# RGBTemp.net
KiCad netlist of a schematic drawn in EAGLE
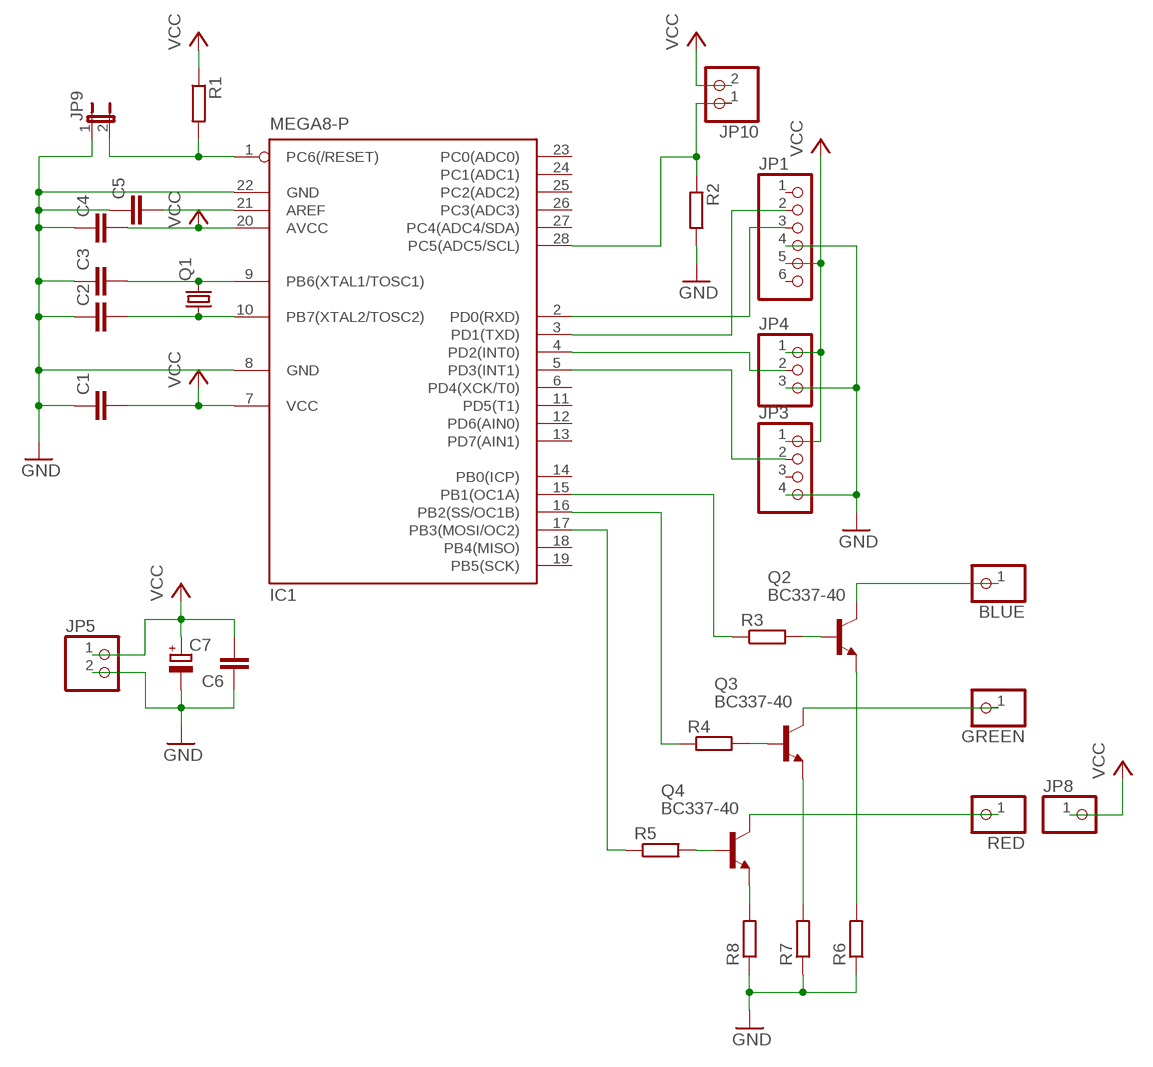
[diagram p0: schematic, sheet 1]

(export (version "E")
  (design (tool "Eeschema 10.0.6"))
  (components
    (comp (ref "BLUE")
      (value "PINHD-1X1")
      (footprint "eagle-import:1X01")
      (libsource (lib "eagle-import") (part "PINHD-1X1"))
    )
    (comp (ref "C1")
      (value "C-EU025-025X050")
      (footprint "eagle-import:C025-025X050")
      (libsource (lib "eagle-import") (part "C-EU025-025X050"))
    )
    (comp (ref "C2")
      (value "C-EU025-025X050")
      (footprint "eagle-import:C025-025X050")
      (libsource (lib "eagle-import") (part "C-EU025-025X050"))
    )
    (comp (ref "C3")
      (value "C-EU025-025X050")
      (footprint "eagle-import:C025-025X050")
      (libsource (lib "eagle-import") (part "C-EU025-025X050"))
    )
    (comp (ref "C4")
      (value "C-EU025-025X050")
      (footprint "eagle-import:C025-025X050")
      (libsource (lib "eagle-import") (part "C-EU025-025X050"))
    )
    (comp (ref "C5")
      (value "C-EU025-025X050")
      (footprint "eagle-import:C025-025X050")
      (libsource (lib "eagle-import") (part "C-EU025-025X050"))
    )
    (comp (ref "C6")
      (value "C-EU025-025X050")
      (footprint "eagle-import:C025-025X050")
      (libsource (lib "eagle-import") (part "C-EU025-025X050"))
    )
    (comp (ref "C7")
      (value "CPOL-EUE5-8.5")
      (footprint "eagle-import:E5-8,5")
      (libsource (lib "eagle-import") (part "CPOL-EUE5-8.5"))
    )
    (comp (ref "GREEN")
      (value "PINHD-1X1")
      (footprint "eagle-import:1X01")
      (libsource (lib "eagle-import") (part "PINHD-1X1"))
    )
    (comp (ref "IC1")
      (value "MEGA8-P")
      (footprint "eagle-import:DIL28-3")
      (libsource (lib "eagle-import") (part "MEGA8-P"))
    )
    (comp (ref "JP1")
      (value "PINHD-1X6")
      (footprint "eagle-import:1X06")
      (libsource (lib "eagle-import") (part "PINHD-1X6"))
    )
    (comp (ref "JP3")
      (value "PINHD-1X4")
      (footprint "eagle-import:1X04")
      (libsource (lib "eagle-import") (part "PINHD-1X4"))
    )
    (comp (ref "JP4")
      (value "PINHD-1X3")
      (footprint "eagle-import:1X03")
      (libsource (lib "eagle-import") (part "PINHD-1X3"))
    )
    (comp (ref "JP5")
      (value "PINHD-1X2")
      (footprint "eagle-import:1X02")
      (libsource (lib "eagle-import") (part "PINHD-1X2"))
    )
    (comp (ref "JP8")
      (value "PINHD-1X1")
      (footprint "eagle-import:1X01")
      (libsource (lib "eagle-import") (part "PINHD-1X1"))
    )
    (comp (ref "JP9")
      (value "JP1E")
      (footprint "eagle-import:JP1")
      (libsource (lib "eagle-import") (part "JP1E"))
    )
    (comp (ref "JP10")
      (value "PINHD-1X2")
      (footprint "eagle-import:1X02")
      (libsource (lib "eagle-import") (part "PINHD-1X2"))
    )
    (comp (ref "Q1")
      (value "CRYSTALHC49U-V")
      (footprint "eagle-import:HC49U-V")
      (libsource (lib "eagle-import") (part "CRYSTALHC49U-V"))
    )
    (comp (ref "Q2")
      (value "BC337-40")
      (footprint "eagle-import:TO92")
      (libsource (lib "eagle-import") (part "BC337-40"))
    )
    (comp (ref "Q3")
      (value "BC337-40")
      (footprint "eagle-import:TO92")
      (libsource (lib "eagle-import") (part "BC337-40"))
    )
    (comp (ref "Q4")
      (value "BC337-40")
      (footprint "eagle-import:TO92")
      (libsource (lib "eagle-import") (part "BC337-40"))
    )
    (comp (ref "R1")
      (value "R-EU_R1206")
      (footprint "eagle-import:R1206")
      (libsource (lib "eagle-import") (part "R-EU_R1206"))
    )
    (comp (ref "R2")
      (value "R-EU_R1206")
      (footprint "eagle-import:R1206")
      (libsource (lib "eagle-import") (part "R-EU_R1206"))
    )
    (comp (ref "R3")
      (value "R-EU_R1206")
      (footprint "eagle-import:R1206")
      (libsource (lib "eagle-import") (part "R-EU_R1206"))
    )
    (comp (ref "R4")
      (value "R-EU_R1206")
      (footprint "eagle-import:R1206")
      (libsource (lib "eagle-import") (part "R-EU_R1206"))
    )
    (comp (ref "R5")
      (value "R-EU_R1206")
      (footprint "eagle-import:R1206")
      (libsource (lib "eagle-import") (part "R-EU_R1206"))
    )
    (comp (ref "R6")
      (value "R-EU_0207/2V")
      (footprint "eagle-import:0207_2V")
      (libsource (lib "eagle-import") (part "R-EU_0207/2V"))
    )
    (comp (ref "R7")
      (value "R-EU_0207/2V")
      (footprint "eagle-import:0207_2V")
      (libsource (lib "eagle-import") (part "R-EU_0207/2V"))
    )
    (comp (ref "R8")
      (value "R-EU_0207/2V")
      (footprint "eagle-import:0207_2V")
      (libsource (lib "eagle-import") (part "R-EU_0207/2V"))
    )
    (comp (ref "RED")
      (value "PINHD-1X1")
      (footprint "eagle-import:1X01")
      (libsource (lib "eagle-import") (part "PINHD-1X1"))
    )
  )
  (nets
    (net (code "1") (name "GND") (class "Default")
      (node (ref "C1") (pin "1") (pinfunction "1_1") (pintype "passive"))
      (node (ref "C2") (pin "1") (pinfunction "1_1") (pintype "passive"))
      (node (ref "C3") (pin "1") (pinfunction "1_1") (pintype "passive"))
      (node (ref "C4") (pin "1") (pinfunction "1_1") (pintype "passive"))
      (node (ref "C5") (pin "1") (pinfunction "1_1") (pintype "passive"))
      (node (ref "C6") (pin "1") (pinfunction "1_1") (pintype "passive"))
      (node (ref "C7") (pin "-") (pinfunction "-_-") (pintype "passive"))
      (node (ref "IC1") (pin "22") (pinfunction "GND_22") (pintype "power_in"))
      (node (ref "IC1") (pin "8") (pinfunction "GND_8") (pintype "power_in"))
      (node (ref "JP1") (pin "4") (pinfunction "4_4") (pintype "passive"))
      (node (ref "JP3") (pin "4") (pinfunction "4_4") (pintype "passive"))
      (node (ref "JP4") (pin "3") (pinfunction "3_3") (pintype "passive"))
      (node (ref "JP5") (pin "2") (pinfunction "2_2") (pintype "passive"))
      (node (ref "JP9") (pin "1") (pinfunction "1_1") (pintype "passive"))
      (node (ref "R2") (pin "2") (pinfunction "2_2") (pintype "passive"))
      (node (ref "R6") (pin "1") (pinfunction "1_1") (pintype "passive"))
      (node (ref "R7") (pin "1") (pinfunction "1_1") (pintype "passive"))
      (node (ref "R8") (pin "1") (pinfunction "1_1") (pintype "passive"))
    )
    (net (code "2") (name "Net-(IC1-AREF)") (class "Default")
      (node (ref "C5") (pin "2") (pinfunction "2_2") (pintype "passive"))
      (node (ref "IC1") (pin "21") (pinfunction "AREF_21") (pintype "passive"))
    )
    (net (code "3") (name "Net-(IC1-PB1(OC1A))") (class "Default")
      (node (ref "IC1") (pin "15") (pinfunction "PB1(OC1A)_15") (pintype "bidirectional"))
      (node (ref "R3") (pin "1") (pinfunction "1_1") (pintype "passive"))
    )
    (net (code "4") (name "Net-(IC1-PB2(SS{slash}OC1B))") (class "Default")
      (node (ref "IC1") (pin "16") (pinfunction "PB2(SS/OC1B)_16") (pintype "bidirectional"))
      (node (ref "R4") (pin "1") (pinfunction "1_1") (pintype "passive"))
    )
    (net (code "5") (name "Net-(IC1-PB3(MOSI{slash}OC2))") (class "Default")
      (node (ref "IC1") (pin "17") (pinfunction "PB3(MOSI/OC2)_17") (pintype "bidirectional"))
      (node (ref "R5") (pin "1") (pinfunction "1_1") (pintype "passive"))
    )
    (net (code "6") (name "Net-(IC1-PB6(XTAL1{slash}TOSC1))") (class "Default")
      (node (ref "C3") (pin "2") (pinfunction "2_2") (pintype "passive"))
      (node (ref "IC1") (pin "9") (pinfunction "PB6(XTAL1/TOSC1)_9") (pintype "bidirectional"))
      (node (ref "Q1") (pin "2") (pinfunction "2_2") (pintype "passive"))
    )
    (net (code "7") (name "Net-(IC1-PB7(XTAL2{slash}TOSC2))") (class "Default")
      (node (ref "C2") (pin "2") (pinfunction "2_2") (pintype "passive"))
      (node (ref "IC1") (pin "10") (pinfunction "PB7(XTAL2/TOSC2)_10") (pintype "bidirectional"))
      (node (ref "Q1") (pin "1") (pinfunction "1_1") (pintype "passive"))
    )
    (net (code "8") (name "Net-(IC1-PC5(ADC5{slash}SCL))") (class "Default")
      (node (ref "IC1") (pin "28") (pinfunction "PC5(ADC5/SCL)_28") (pintype "bidirectional"))
      (node (ref "JP10") (pin "1") (pinfunction "1_1") (pintype "passive"))
      (node (ref "R2") (pin "1") (pinfunction "1_1") (pintype "passive"))
    )
    (net (code "9") (name "Net-(IC1-PC6({slash}RESET))") (class "Default")
      (node (ref "IC1") (pin "1") (pinfunction "PC6(/RESET)_1") (pintype "bidirectional"))
      (node (ref "JP9") (pin "2") (pinfunction "2_2") (pintype "passive"))
      (node (ref "R1") (pin "2") (pinfunction "2_2") (pintype "passive"))
    )
    (net (code "10") (name "Net-(IC1-PD0(RXD))") (class "Default")
      (node (ref "IC1") (pin "2") (pinfunction "PD0(RXD)_2") (pintype "bidirectional"))
      (node (ref "JP1") (pin "3") (pinfunction "3_3") (pintype "passive"))
    )
    (net (code "11") (name "Net-(IC1-PD1(TXD))") (class "Default")
      (node (ref "IC1") (pin "3") (pinfunction "PD1(TXD)_3") (pintype "bidirectional"))
      (node (ref "JP1") (pin "2") (pinfunction "2_2") (pintype "passive"))
    )
    (net (code "12") (name "Net-(IC1-PD2(INT0))") (class "Default")
      (node (ref "IC1") (pin "4") (pinfunction "PD2(INT0)_4") (pintype "bidirectional"))
      (node (ref "JP4") (pin "2") (pinfunction "2_2") (pintype "passive"))
    )
    (net (code "13") (name "Net-(IC1-PD3(INT1))") (class "Default")
      (node (ref "IC1") (pin "5") (pinfunction "PD3(INT1)_5") (pintype "bidirectional"))
      (node (ref "JP3") (pin "2") (pinfunction "2_2") (pintype "passive"))
    )
    (net (code "14") (name "Net-(Q2-B)") (class "Default")
      (node (ref "Q2") (pin "2") (pinfunction "B_2") (pintype "passive"))
      (node (ref "R3") (pin "2") (pinfunction "2_2") (pintype "passive"))
    )
    (net (code "15") (name "Net-(Q2-C)") (class "Default")
      (node (ref "BLUE") (pin "1") (pinfunction "1_1") (pintype "passive"))
      (node (ref "Q2") (pin "3") (pinfunction "C_3") (pintype "passive"))
    )
    (net (code "16") (name "Net-(Q2-E)") (class "Default")
      (node (ref "Q2") (pin "1") (pinfunction "E_1") (pintype "passive"))
      (node (ref "R6") (pin "2") (pinfunction "2_2") (pintype "passive"))
    )
    (net (code "17") (name "Net-(Q3-B)") (class "Default")
      (node (ref "Q3") (pin "2") (pinfunction "B_2") (pintype "passive"))
      (node (ref "R4") (pin "2") (pinfunction "2_2") (pintype "passive"))
    )
    (net (code "18") (name "Net-(Q3-C)") (class "Default")
      (node (ref "GREEN") (pin "1") (pinfunction "1_1") (pintype "passive"))
      (node (ref "Q3") (pin "3") (pinfunction "C_3") (pintype "passive"))
    )
    (net (code "19") (name "Net-(Q3-E)") (class "Default")
      (node (ref "Q3") (pin "1") (pinfunction "E_1") (pintype "passive"))
      (node (ref "R7") (pin "2") (pinfunction "2_2") (pintype "passive"))
    )
    (net (code "20") (name "Net-(Q4-B)") (class "Default")
      (node (ref "Q4") (pin "2") (pinfunction "B_2") (pintype "passive"))
      (node (ref "R5") (pin "2") (pinfunction "2_2") (pintype "passive"))
    )
    (net (code "21") (name "Net-(Q4-C)") (class "Default")
      (node (ref "Q4") (pin "3") (pinfunction "C_3") (pintype "passive"))
      (node (ref "RED") (pin "1") (pinfunction "1_1") (pintype "passive"))
    )
    (net (code "22") (name "Net-(Q4-E)") (class "Default")
      (node (ref "Q4") (pin "1") (pinfunction "E_1") (pintype "passive"))
      (node (ref "R8") (pin "2") (pinfunction "2_2") (pintype "passive"))
    )
    (net (code "23") (name "VCC") (class "Default")
      (node (ref "C1") (pin "2") (pinfunction "2_2") (pintype "passive"))
      (node (ref "C4") (pin "2") (pinfunction "2_2") (pintype "passive"))
      (node (ref "C6") (pin "2") (pinfunction "2_2") (pintype "passive"))
      (node (ref "C7") (pin "+") (pinfunction "+_+") (pintype "passive"))
      (node (ref "IC1") (pin "20") (pinfunction "AVCC_20") (pintype "power_in"))
      (node (ref "IC1") (pin "7") (pinfunction "VCC_7") (pintype "power_in"))
      (node (ref "JP1") (pin "5") (pinfunction "5_5") (pintype "passive"))
      (node (ref "JP10") (pin "2") (pinfunction "2_2") (pintype "passive"))
      (node (ref "JP3") (pin "1") (pinfunction "1_1") (pintype "passive"))
      (node (ref "JP4") (pin "1") (pinfunction "1_1") (pintype "passive"))
      (node (ref "JP5") (pin "1") (pinfunction "1_1") (pintype "passive"))
      (node (ref "JP8") (pin "1") (pinfunction "1_1") (pintype "passive"))
      (node (ref "R1") (pin "1") (pinfunction "1_1") (pintype "passive"))
    )
    (net (code "24") (name "unconnected-(IC1-PB0(ICP)-Pad14)") (class "Default")
      (node (ref "IC1") (pin "14") (pinfunction "PB0(ICP)_14") (pintype "bidirectional"))
    )
    (net (code "25") (name "unconnected-(IC1-PB4(MISO)-Pad18)") (class "Default")
      (node (ref "IC1") (pin "18") (pinfunction "PB4(MISO)_18") (pintype "bidirectional"))
    )
    (net (code "26") (name "unconnected-(IC1-PB5(SCK)-Pad19)") (class "Default")
      (node (ref "IC1") (pin "19") (pinfunction "PB5(SCK)_19") (pintype "bidirectional"))
    )
    (net (code "27") (name "unconnected-(IC1-PC0(ADC0)-Pad23)") (class "Default")
      (node (ref "IC1") (pin "23") (pinfunction "PC0(ADC0)_23") (pintype "bidirectional"))
    )
    (net (code "28") (name "unconnected-(IC1-PC1(ADC1)-Pad24)") (class "Default")
      (node (ref "IC1") (pin "24") (pinfunction "PC1(ADC1)_24") (pintype "bidirectional"))
    )
    (net (code "29") (name "unconnected-(IC1-PC2(ADC2)-Pad25)") (class "Default")
      (node (ref "IC1") (pin "25") (pinfunction "PC2(ADC2)_25") (pintype "bidirectional"))
    )
    (net (code "30") (name "unconnected-(IC1-PC3(ADC3)-Pad26)") (class "Default")
      (node (ref "IC1") (pin "26") (pinfunction "PC3(ADC3)_26") (pintype "bidirectional"))
    )
    (net (code "31") (name "unconnected-(IC1-PC4(ADC4{slash}SDA)-Pad27)") (class "Default")
      (node (ref "IC1") (pin "27") (pinfunction "PC4(ADC4/SDA)_27") (pintype "bidirectional"))
    )
    (net (code "32") (name "unconnected-(IC1-PD4(XCK{slash}T0)-Pad6)") (class "Default")
      (node (ref "IC1") (pin "6") (pinfunction "PD4(XCK/T0)_6") (pintype "bidirectional"))
    )
    (net (code "33") (name "unconnected-(IC1-PD5(T1)-Pad11)") (class "Default")
      (node (ref "IC1") (pin "11") (pinfunction "PD5(T1)_11") (pintype "bidirectional"))
    )
    (net (code "34") (name "unconnected-(IC1-PD6(AIN0)-Pad12)") (class "Default")
      (node (ref "IC1") (pin "12") (pinfunction "PD6(AIN0)_12") (pintype "bidirectional"))
    )
    (net (code "35") (name "unconnected-(IC1-PD7(AIN1)-Pad13)") (class "Default")
      (node (ref "IC1") (pin "13") (pinfunction "PD7(AIN1)_13") (pintype "bidirectional"))
    )
    (net (code "36") (name "unconnected-(JP1-Pad1)") (class "Default")
      (node (ref "JP1") (pin "1") (pinfunction "1_1") (pintype "passive"))
    )
    (net (code "37") (name "unconnected-(JP1-Pad6)") (class "Default")
      (node (ref "JP1") (pin "6") (pinfunction "6_6") (pintype "passive"))
    )
    (net (code "38") (name "unconnected-(JP3-Pad3)") (class "Default")
      (node (ref "JP3") (pin "3") (pinfunction "3_3") (pintype "passive"))
    )
  )
)
